# vfd_drive.net
KiCad netlist of a schematic drawn in EAGLE
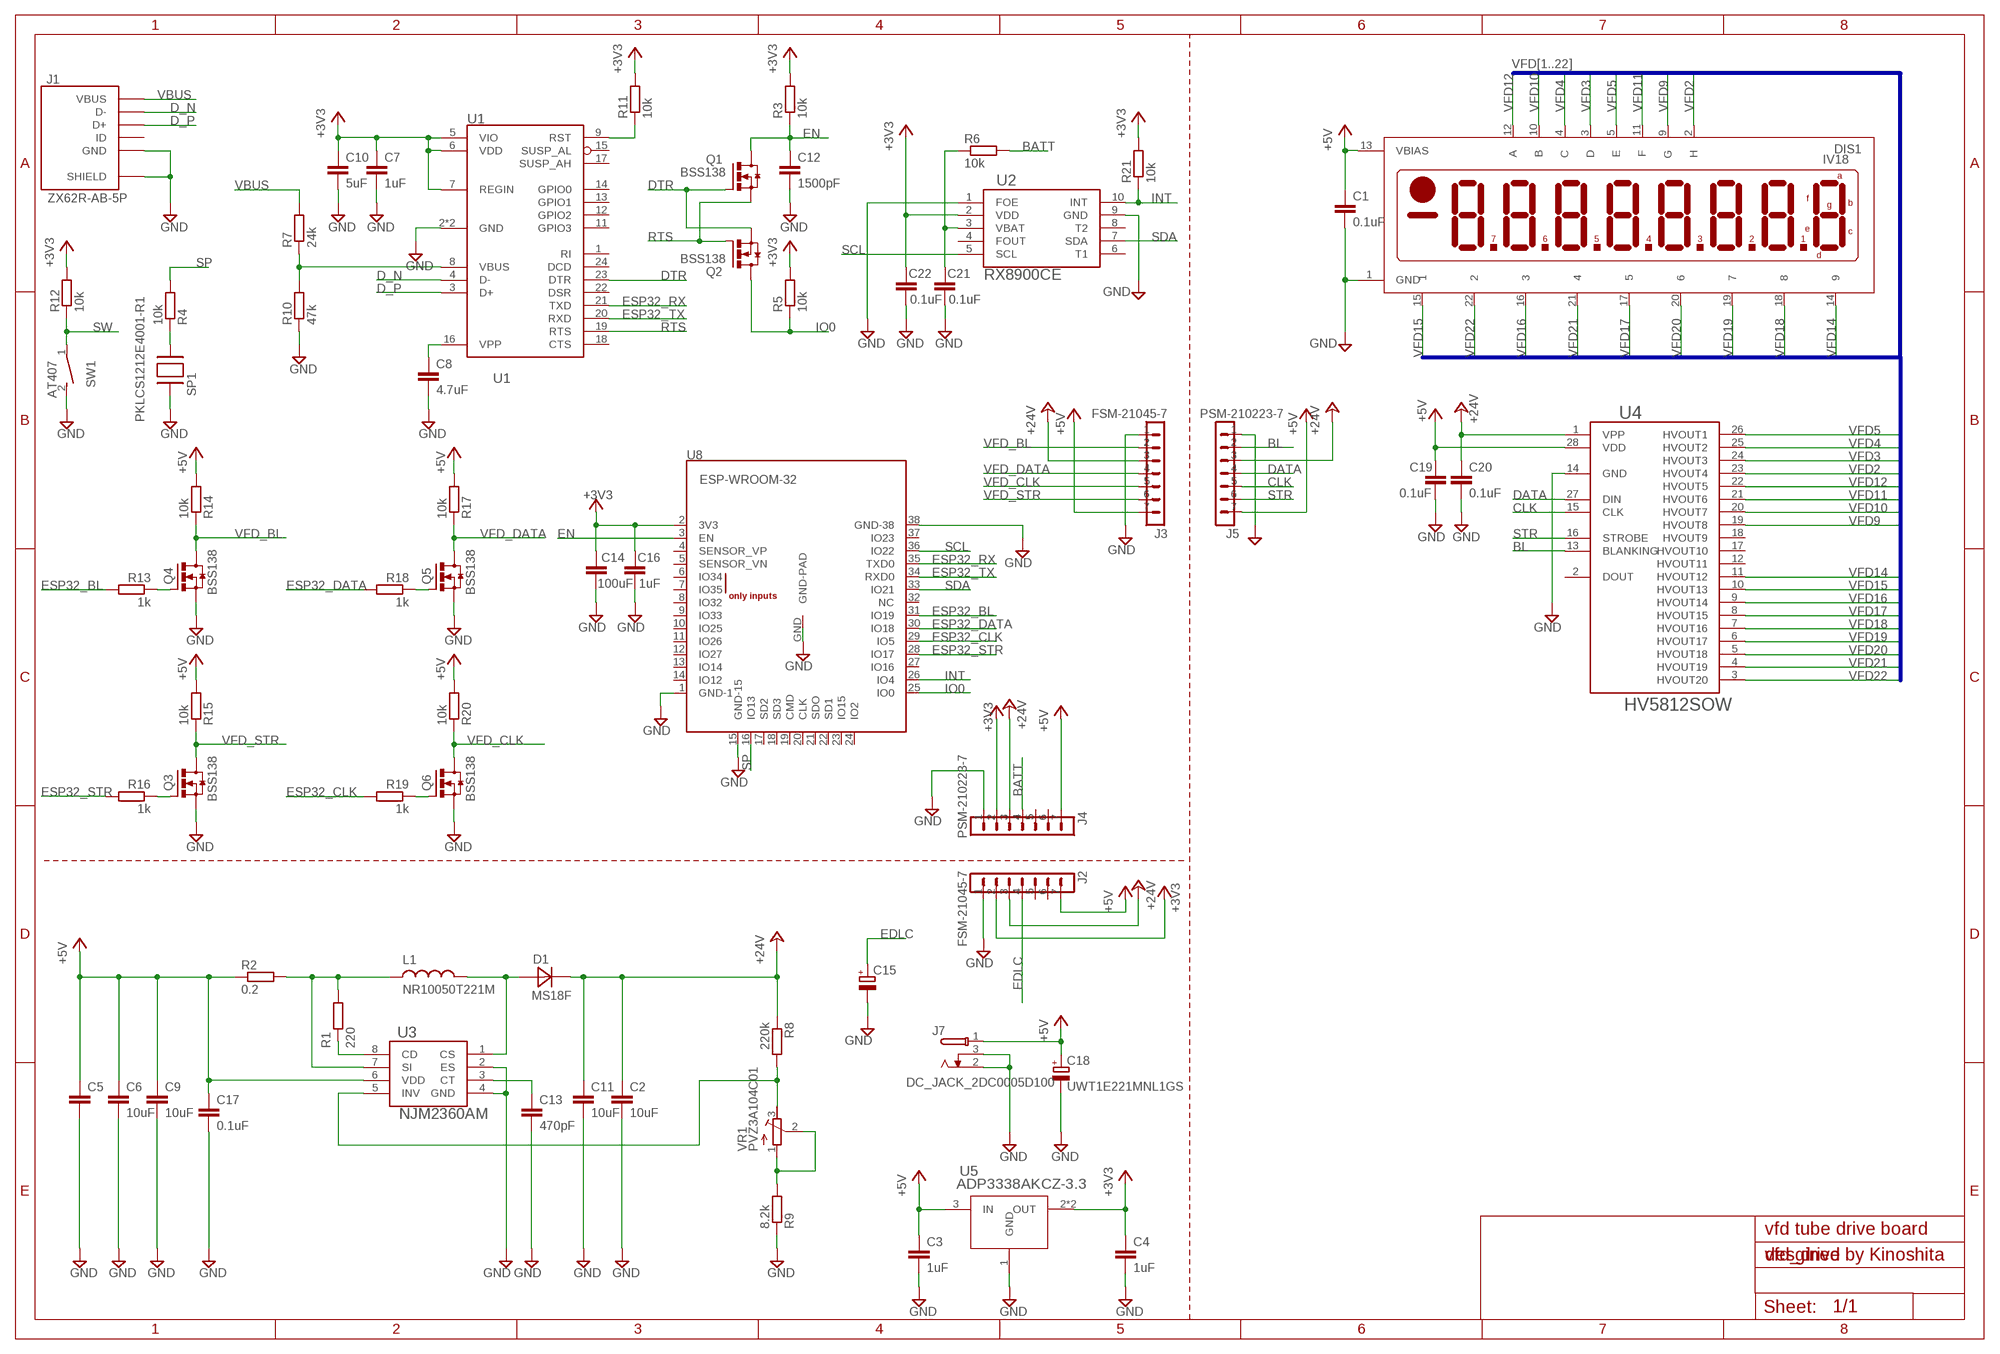
[diagram p0: schematic, sheet 1]

(export (version "E")
  (design (tool "Eeschema 10.0.6"))
  (components
    (comp (ref "C1")
      (value "0.1uF")
      (footprint "eagle-import:C0603")
      (libsource (lib "eagle-import") (part "C-EUC0603"))
    )
    (comp (ref "C2")
      (value "10uF")
      (footprint "eagle-import:C3216")
      (libsource (lib "eagle-import") (part "C-EUC3216"))
    )
    (comp (ref "C3")
      (value "1uF")
      (footprint "eagle-import:C0603")
      (libsource (lib "eagle-import") (part "C-EUC0603"))
    )
    (comp (ref "C4")
      (value "1uF")
      (footprint "eagle-import:C0603")
      (libsource (lib "eagle-import") (part "C-EUC0603"))
    )
    (comp (ref "C5")
      (value "C-EUC3225")
      (footprint "eagle-import:C3225")
      (libsource (lib "eagle-import") (part "C-EUC3225"))
    )
    (comp (ref "C6")
      (value "10uF")
      (footprint "eagle-import:C0603")
      (libsource (lib "eagle-import") (part "C-EUC0603"))
    )
    (comp (ref "C7")
      (value "1uF")
      (footprint "eagle-import:C0603")
      (libsource (lib "eagle-import") (part "C-EUC0603"))
    )
    (comp (ref "C8")
      (value "4.7uF")
      (footprint "eagle-import:C0603")
      (libsource (lib "eagle-import") (part "C-EUC0603"))
    )
    (comp (ref "C9")
      (value "10uF")
      (footprint "eagle-import:C0603")
      (libsource (lib "eagle-import") (part "C-EUC0603"))
    )
    (comp (ref "C10")
      (value "5uF")
      (footprint "eagle-import:C0603")
      (libsource (lib "eagle-import") (part "C-EUC0603"))
    )
    (comp (ref "C11")
      (value "10uF")
      (footprint "eagle-import:C3216")
      (libsource (lib "eagle-import") (part "C-EUC3216"))
    )
    (comp (ref "C12")
      (value "1500pF")
      (footprint "eagle-import:C0603")
      (libsource (lib "eagle-import") (part "C-EUC0603"))
    )
    (comp (ref "C13")
      (value "470pF")
      (footprint "eagle-import:C0603")
      (libsource (lib "eagle-import") (part "C-EUC0603"))
    )
    (comp (ref "C14")
      (value "100uF")
      (footprint "eagle-import:C1206")
      (libsource (lib "eagle-import") (part "C-EUC1206"))
    )
    (comp (ref "C15")
      (value "CPOL-EUSE-5R5-D155VY")
      (footprint "eagle-import:SE-5R5-D155VY")
      (libsource (lib "eagle-import") (part "CPOL-EUSE-5R5-D155VY"))
    )
    (comp (ref "C16")
      (value "1uF")
      (footprint "eagle-import:C0603")
      (libsource (lib "eagle-import") (part "C-EUC0603"))
    )
    (comp (ref "C17")
      (value "0.1uF")
      (footprint "eagle-import:C0603")
      (libsource (lib "eagle-import") (part "C-EUC0603"))
    )
    (comp (ref "C18")
      (value "UWT1E221MNL1GS")
      (footprint "eagle-import:NICHICON-ALMINUM-CAPACITOR-8MM")
      (libsource (lib "eagle-import") (part "UWT1E221MNL1GS"))
    )
    (comp (ref "C19")
      (value "0.1uF")
      (footprint "eagle-import:C0603")
      (libsource (lib "eagle-import") (part "C-EUC0603"))
    )
    (comp (ref "C20")
      (value "0.1uF")
      (footprint "eagle-import:C0603")
      (libsource (lib "eagle-import") (part "C-EUC0603"))
    )
    (comp (ref "C21")
      (value "0.1uF")
      (footprint "eagle-import:C0603")
      (libsource (lib "eagle-import") (part "C-EUC0603"))
    )
    (comp (ref "C22")
      (value "0.1uF")
      (footprint "eagle-import:C0603")
      (libsource (lib "eagle-import") (part "C-EUC0603"))
    )
    (comp (ref "D1")
      (value "MS18F")
      (footprint "eagle-import:SMAF")
      (libsource (lib "eagle-import") (part "MS18F"))
    )
    (comp (ref "DIS1")
      (value "IV18")
      (footprint "eagle-import:IV18")
      (libsource (lib "eagle-import") (part "IV18"))
    )
    (comp (ref "J1")
      (value "ZX62R-AB-5P")
      (footprint "eagle-import:ZX62R-B-5PA")
      (libsource (lib "eagle-import") (part "ZX62R-AB-5P"))
    )
    (comp (ref "J2")
      (value "FSM-21045-7")
      (footprint "eagle-import:FSM-21045-7")
      (libsource (lib "eagle-import") (part "FSM-21045-7"))
    )
    (comp (ref "J3")
      (value "FSM-21045-7")
      (footprint "eagle-import:FSM-21045-7")
      (libsource (lib "eagle-import") (part "FSM-21045-7"))
    )
    (comp (ref "J4")
      (value "PSM-210223-7")
      (footprint "eagle-import:PSM-210223-7")
      (libsource (lib "eagle-import") (part "PSM-210223-7"))
    )
    (comp (ref "J5")
      (value "PSM-210223-7")
      (footprint "eagle-import:PSM-210223-7")
      (libsource (lib "eagle-import") (part "PSM-210223-7"))
    )
    (comp (ref "J7")
      (value "DC_JACK_2DC0005D100")
      (footprint "eagle-import:DC_JACK_2DC0005D100")
      (libsource (lib "eagle-import") (part "DC_JACK_2DC0005D100"))
    )
    (comp (ref "L1")
      (value "NR10050T221M")
      (footprint "eagle-import:NR10050T100M")
      (libsource (lib "eagle-import") (part "NR10050T221M"))
    )
    (comp (ref "Q1")
      (value "BSS138")
      (footprint "eagle-import:SOT23-N-MOSFET")
      (libsource (lib "eagle-import") (part "BSS138"))
    )
    (comp (ref "Q2")
      (value "BSS138")
      (footprint "eagle-import:SOT23-N-MOSFET")
      (libsource (lib "eagle-import") (part "BSS138"))
    )
    (comp (ref "Q3")
      (value "BSS138")
      (footprint "eagle-import:SOT23-N-MOSFET")
      (libsource (lib "eagle-import") (part "BSS138"))
    )
    (comp (ref "Q4")
      (value "BSS138")
      (footprint "eagle-import:SOT23-N-MOSFET")
      (libsource (lib "eagle-import") (part "BSS138"))
    )
    (comp (ref "Q5")
      (value "BSS138")
      (footprint "eagle-import:SOT23-N-MOSFET")
      (libsource (lib "eagle-import") (part "BSS138"))
    )
    (comp (ref "Q6")
      (value "BSS138")
      (footprint "eagle-import:SOT23-N-MOSFET")
      (libsource (lib "eagle-import") (part "BSS138"))
    )
    (comp (ref "R1")
      (value "220")
      (footprint "eagle-import:R0603")
      (libsource (lib "eagle-import") (part "R-EU_R0603"))
    )
    (comp (ref "R2")
      (value "0.2")
      (footprint "eagle-import:R1206")
      (libsource (lib "eagle-import") (part "R-EU_R1206"))
    )
    (comp (ref "R3")
      (value "10k")
      (footprint "eagle-import:R0603")
      (libsource (lib "eagle-import") (part "R-EU_R0603"))
    )
    (comp (ref "R4")
      (value "10k")
      (footprint "eagle-import:R0603")
      (libsource (lib "eagle-import") (part "R-EU_R0603"))
    )
    (comp (ref "R5")
      (value "10k")
      (footprint "eagle-import:R0603")
      (libsource (lib "eagle-import") (part "R-EU_R0603"))
    )
    (comp (ref "R6")
      (value "10k")
      (footprint "eagle-import:R0603")
      (libsource (lib "eagle-import") (part "R-EU_R0603"))
    )
    (comp (ref "R7")
      (value "24k")
      (footprint "eagle-import:R0603")
      (libsource (lib "eagle-import") (part "R-EU_R0603"))
    )
    (comp (ref "R8")
      (value "220k")
      (footprint "eagle-import:R0603")
      (libsource (lib "eagle-import") (part "R-EU_R0603"))
    )
    (comp (ref "R9")
      (value "8.2k")
      (footprint "eagle-import:R0603")
      (libsource (lib "eagle-import") (part "R-EU_R0603"))
    )
    (comp (ref "R10")
      (value "47k")
      (footprint "eagle-import:R0603")
      (libsource (lib "eagle-import") (part "R-EU_R0603"))
    )
    (comp (ref "R11")
      (value "10k")
      (footprint "eagle-import:R0603")
      (libsource (lib "eagle-import") (part "R-EU_R0603"))
    )
    (comp (ref "R12")
      (value "10k")
      (footprint "eagle-import:R0603")
      (libsource (lib "eagle-import") (part "R-EU_R0603"))
    )
    (comp (ref "R13")
      (value "1k")
      (footprint "eagle-import:R0603")
      (libsource (lib "eagle-import") (part "R-EU_R0603"))
    )
    (comp (ref "R14")
      (value "10k")
      (footprint "eagle-import:R0603")
      (libsource (lib "eagle-import") (part "R-EU_R0603"))
    )
    (comp (ref "R15")
      (value "10k")
      (footprint "eagle-import:R0603")
      (libsource (lib "eagle-import") (part "R-EU_R0603"))
    )
    (comp (ref "R16")
      (value "1k")
      (footprint "eagle-import:R0603")
      (libsource (lib "eagle-import") (part "R-EU_R0603"))
    )
    (comp (ref "R17")
      (value "10k")
      (footprint "eagle-import:R0603")
      (libsource (lib "eagle-import") (part "R-EU_R0603"))
    )
    (comp (ref "R18")
      (value "1k")
      (footprint "eagle-import:R0603")
      (libsource (lib "eagle-import") (part "R-EU_R0603"))
    )
    (comp (ref "R19")
      (value "1k")
      (footprint "eagle-import:R0603")
      (libsource (lib "eagle-import") (part "R-EU_R0603"))
    )
    (comp (ref "R20")
      (value "10k")
      (footprint "eagle-import:R0603")
      (libsource (lib "eagle-import") (part "R-EU_R0603"))
    )
    (comp (ref "R21")
      (value "10k")
      (footprint "eagle-import:R0603")
      (libsource (lib "eagle-import") (part "R-EU_R0603"))
    )
    (comp (ref "SP1")
      (value "PKLCS1212E4001-R1")
      (footprint "eagle-import:PKLCS1212E4001-R1")
      (libsource (lib "eagle-import") (part "PKLCS1212E4001-R1"))
    )
    (comp (ref "SW1")
      (value "AT407")
      (footprint "eagle-import:AT407")
      (libsource (lib "eagle-import") (part "AT407"))
    )
    (comp (ref "U1")
      (value "CP2104")
      (footprint "eagle-import:QFN24-SILABS")
      (libsource (lib "eagle-import") (part "CP2104"))
    )
    (comp (ref "U2")
      (value "RX8900CE")
      (footprint "eagle-import:RX8900CE")
      (libsource (lib "eagle-import") (part "RX8900CE"))
    )
    (comp (ref "U3")
      (value "NJM2360AM")
      (footprint "eagle-import:DMP8")
      (libsource (lib "eagle-import") (part "NJM2360AM"))
    )
    (comp (ref "U4")
      (value "HV5812SOW")
      (footprint "eagle-import:SOW28-MICROCHIP")
      (libsource (lib "eagle-import") (part "HV5812SOW"))
    )
    (comp (ref "U5")
      (value "ADP3338AKCZ-3.3")
      (footprint "eagle-import:SOT233")
      (libsource (lib "eagle-import") (part "ADP3338AKCZ-3.3"))
    )
    (comp (ref "U8")
      (value "ESP-WROOM-32")
      (footprint "eagle-import:ESP-WROOM-32")
      (libsource (lib "eagle-import") (part "ESP-WROOM-32"))
    )
    (comp (ref "VR1")
      (value "PVZ3A104C01")
      (footprint "eagle-import:PVZ3A")
      (libsource (lib "eagle-import") (part "PVZ3A104C01"))
    )
  )
  (nets
    (net (code "6") (name "+3V3") (class "Default")
      (node (ref "C10") (pin "1") (pinfunction "1_1") (pintype "passive"))
      (node (ref "C14") (pin "1") (pinfunction "1_1") (pintype "passive"))
      (node (ref "C16") (pin "1") (pinfunction "1_1") (pintype "passive"))
      (node (ref "C22") (pin "1") (pinfunction "1_1") (pintype "passive"))
      (node (ref "C4") (pin "1") (pinfunction "1_1") (pintype "passive"))
      (node (ref "C7") (pin "1") (pinfunction "1_1") (pintype "passive"))
      (node (ref "J2") (pin "2") (pinfunction "2_2") (pintype "bidirectional"))
      (node (ref "J4") (pin "2") (pinfunction "2_2") (pintype "bidirectional"))
      (node (ref "R11") (pin "2") (pinfunction "2_2") (pintype "passive"))
      (node (ref "R12") (pin "2") (pinfunction "2_2") (pintype "passive"))
      (node (ref "R21") (pin "2") (pinfunction "2_2") (pintype "passive"))
      (node (ref "R3") (pin "2") (pinfunction "2_2") (pintype "passive"))
      (node (ref "R5") (pin "2") (pinfunction "2_2") (pintype "passive"))
      (node (ref "U1") (pin "5") (pinfunction "VIO_5") (pintype "bidirectional"))
      (node (ref "U1") (pin "6") (pinfunction "VDD_6") (pintype "bidirectional"))
      (node (ref "U1") (pin "7") (pinfunction "REGIN_7") (pintype "bidirectional"))
      (node (ref "U2") (pin "2") (pinfunction "VDD_2") (pintype "bidirectional"))
      (node (ref "U5") (pin "2") (pinfunction "OUT_2") (pintype "passive"))
      (node (ref "U5") (pin "4") (pinfunction "OUT_4") (pintype "passive"))
      (node (ref "U8") (pin "2") (pinfunction "3V3_2") (pintype "bidirectional"))
    )
    (net (code "7") (name "+5V") (class "Default")
      (node (ref "C1") (pin "1") (pinfunction "1_1") (pintype "passive"))
      (node (ref "C17") (pin "1") (pinfunction "1_1") (pintype "passive"))
      (node (ref "C18") (pin "POS") (pinfunction "+_POS") (pintype "passive"))
      (node (ref "C19") (pin "1") (pinfunction "1_1") (pintype "passive"))
      (node (ref "C3") (pin "1") (pinfunction "1_1") (pintype "passive"))
      (node (ref "C5") (pin "1") (pinfunction "1_1") (pintype "passive"))
      (node (ref "C6") (pin "1") (pinfunction "1_1") (pintype "passive"))
      (node (ref "C9") (pin "1") (pinfunction "1_1") (pintype "passive"))
      (node (ref "DIS1") (pin "13") (pinfunction "VBIAS_13") (pintype "power_in"))
      (node (ref "J2") (pin "7") (pinfunction "7_7") (pintype "bidirectional"))
      (node (ref "J3") (pin "7") (pinfunction "7_7") (pintype "bidirectional"))
      (node (ref "J4") (pin "7") (pinfunction "7_7") (pintype "bidirectional"))
      (node (ref "J5") (pin "7") (pinfunction "7_7") (pintype "bidirectional"))
      (node (ref "J7") (pin "1") (pinfunction "1_1") (pintype "passive"))
      (node (ref "R14") (pin "2") (pinfunction "2_2") (pintype "passive"))
      (node (ref "R15") (pin "2") (pinfunction "2_2") (pintype "passive"))
      (node (ref "R17") (pin "2") (pinfunction "2_2") (pintype "passive"))
      (node (ref "R2") (pin "1") (pinfunction "1_1") (pintype "passive"))
      (node (ref "R20") (pin "2") (pinfunction "2_2") (pintype "passive"))
      (node (ref "U3") (pin "6") (pinfunction "VDD_6") (pintype "bidirectional"))
      (node (ref "U4") (pin "28") (pinfunction "VDD_28") (pintype "bidirectional"))
      (node (ref "U5") (pin "3") (pinfunction "IN_3") (pintype "passive"))
    )
    (net (code "8") (name "+24V") (class "Default")
      (node (ref "C11") (pin "1") (pinfunction "1_1") (pintype "passive"))
      (node (ref "C2") (pin "1") (pinfunction "1_1") (pintype "passive"))
      (node (ref "C20") (pin "1") (pinfunction "1_1") (pintype "passive"))
      (node (ref "D1") (pin "K") (pinfunction "C_K") (pintype "passive"))
      (node (ref "J2") (pin "3") (pinfunction "3_3") (pintype "bidirectional"))
      (node (ref "J3") (pin "3") (pinfunction "3_3") (pintype "bidirectional"))
      (node (ref "J4") (pin "3") (pinfunction "3_3") (pintype "bidirectional"))
      (node (ref "J5") (pin "3") (pinfunction "3_3") (pintype "bidirectional"))
      (node (ref "R8") (pin "1") (pinfunction "1_1") (pintype "passive"))
      (node (ref "U4") (pin "1") (pinfunction "VPP_1") (pintype "bidirectional"))
    )
    (net (code "9") (name "/BATT") (class "Default")
      (node (ref "J4") (pin "4") (pinfunction "4_4") (pintype "bidirectional"))
      (node (ref "R6") (pin "2") (pinfunction "2_2") (pintype "passive"))
    )
    (net (code "10") (name "/BL") (class "Default")
      (node (ref "J5") (pin "2") (pinfunction "2_2") (pintype "bidirectional"))
      (node (ref "U4") (pin "13") (pinfunction "BLANKING_13") (pintype "bidirectional"))
    )
    (net (code "11") (name "/CLK") (class "Default")
      (node (ref "J5") (pin "5") (pinfunction "5_5") (pintype "bidirectional"))
      (node (ref "U4") (pin "15") (pinfunction "CLK_15") (pintype "bidirectional"))
    )
    (net (code "12") (name "/DATA") (class "Default")
      (node (ref "J5") (pin "4") (pinfunction "4_4") (pintype "bidirectional"))
      (node (ref "U4") (pin "27") (pinfunction "DIN_27") (pintype "bidirectional"))
    )
    (net (code "13") (name "/DTR") (class "Default")
      (node (ref "Q1") (pin "G") (pinfunction "G_G") (pintype "passive"))
      (node (ref "Q2") (pin "S") (pinfunction "S_S") (pintype "passive"))
      (node (ref "U1") (pin "23") (pinfunction "DTR_23") (pintype "bidirectional"))
    )
    (net (code "14") (name "/D_N") (class "Default")
      (node (ref "J1") (pin "D-") (pinfunction "D-_D-") (pintype "bidirectional"))
      (node (ref "U1") (pin "4") (pinfunction "D-_4") (pintype "bidirectional"))
    )
    (net (code "15") (name "/D_P") (class "Default")
      (node (ref "J1") (pin "D+") (pinfunction "D+_D+") (pintype "bidirectional"))
      (node (ref "U1") (pin "3") (pinfunction "D+_3") (pintype "bidirectional"))
    )
    (net (code "16") (name "/EDLC") (class "Default")
      (node (ref "C15") (pin "POS") (pinfunction "+_POS") (pintype "passive"))
      (node (ref "J2") (pin "4") (pinfunction "4_4") (pintype "bidirectional"))
    )
    (net (code "17") (name "/EN") (class "Default")
      (node (ref "C12") (pin "1") (pinfunction "1_1") (pintype "passive"))
      (node (ref "Q1") (pin "D") (pinfunction "D_D") (pintype "passive"))
      (node (ref "R3") (pin "1") (pinfunction "1_1") (pintype "passive"))
      (node (ref "U8") (pin "3") (pinfunction "EN_3") (pintype "bidirectional"))
    )
    (net (code "18") (name "/ESP32_BL") (class "Default")
      (node (ref "R13") (pin "2") (pinfunction "2_2") (pintype "passive"))
      (node (ref "U8") (pin "31") (pinfunction "IO19_31") (pintype "bidirectional"))
    )
    (net (code "19") (name "/ESP32_CLK") (class "Default")
      (node (ref "R19") (pin "2") (pinfunction "2_2") (pintype "passive"))
      (node (ref "U8") (pin "29") (pinfunction "IO5_29") (pintype "bidirectional"))
    )
    (net (code "20") (name "/ESP32_DATA") (class "Default")
      (node (ref "R18") (pin "2") (pinfunction "2_2") (pintype "passive"))
      (node (ref "U8") (pin "30") (pinfunction "IO18_30") (pintype "bidirectional"))
    )
    (net (code "21") (name "/ESP32_RX") (class "Default")
      (node (ref "U1") (pin "21") (pinfunction "TXD_21") (pintype "bidirectional"))
      (node (ref "U8") (pin "35") (pinfunction "TXD0_35") (pintype "bidirectional"))
    )
    (net (code "22") (name "/ESP32_STR") (class "Default")
      (node (ref "R16") (pin "2") (pinfunction "2_2") (pintype "passive"))
      (node (ref "U8") (pin "28") (pinfunction "IO17_28") (pintype "bidirectional"))
    )
    (net (code "23") (name "/ESP32_TX") (class "Default")
      (node (ref "U1") (pin "20") (pinfunction "RXD_20") (pintype "bidirectional"))
      (node (ref "U8") (pin "34") (pinfunction "RXD0_34") (pintype "bidirectional"))
    )
    (net (code "24") (name "/INT") (class "Default")
      (node (ref "R21") (pin "1") (pinfunction "1_1") (pintype "passive"))
      (node (ref "U2") (pin "10") (pinfunction "INT_10") (pintype "bidirectional"))
      (node (ref "U8") (pin "26") (pinfunction "IO4_26") (pintype "bidirectional"))
    )
    (net (code "25") (name "/IO0") (class "Default")
      (node (ref "Q2") (pin "D") (pinfunction "D_D") (pintype "passive"))
      (node (ref "R5") (pin "1") (pinfunction "1_1") (pintype "passive"))
      (node (ref "U8") (pin "25") (pinfunction "IO0_25") (pintype "bidirectional"))
    )
    (net (code "26") (name "/RTS") (class "Default")
      (node (ref "Q1") (pin "S") (pinfunction "S_S") (pintype "passive"))
      (node (ref "Q2") (pin "G") (pinfunction "G_G") (pintype "passive"))
      (node (ref "U1") (pin "19") (pinfunction "RTS_19") (pintype "bidirectional"))
    )
    (net (code "27") (name "/SCL") (class "Default")
      (node (ref "U2") (pin "5") (pinfunction "SCL_5") (pintype "bidirectional"))
      (node (ref "U8") (pin "36") (pinfunction "IO22_36") (pintype "bidirectional"))
    )
    (net (code "28") (name "/SDA") (class "Default")
      (node (ref "U2") (pin "7") (pinfunction "SDA_7") (pintype "bidirectional"))
      (node (ref "U8") (pin "33") (pinfunction "IO21_33") (pintype "bidirectional"))
    )
    (net (code "29") (name "/SP") (class "Default")
      (node (ref "R4") (pin "2") (pinfunction "2_2") (pintype "passive"))
      (node (ref "U8") (pin "16") (pinfunction "IO13_16") (pintype "bidirectional"))
    )
    (net (code "30") (name "/STR") (class "Default")
      (node (ref "J5") (pin "6") (pinfunction "6_6") (pintype "bidirectional"))
      (node (ref "U4") (pin "16") (pinfunction "STROBE_16") (pintype "bidirectional"))
    )
    (net (code "31") (name "/SW") (class "Default")
      (node (ref "R12") (pin "1") (pinfunction "1_1") (pintype "passive"))
      (node (ref "SW1") (pin "1") (pinfunction "1_1") (pintype "passive"))
    )
    (net (code "32") (name "/VBUS") (class "Default")
      (node (ref "J1") (pin "VCC") (pinfunction "VBUS_VCC") (pintype "bidirectional"))
      (node (ref "R7") (pin "2") (pinfunction "2_2") (pintype "passive"))
    )
    (net (code "33") (name "/VFD2") (class "Default")
      (node (ref "DIS1") (pin "2") (pinfunction "H_2") (pintype "passive"))
      (node (ref "U4") (pin "23") (pinfunction "HVOUT4_23") (pintype "bidirectional"))
    )
    (net (code "34") (name "/VFD3") (class "Default")
      (node (ref "DIS1") (pin "3") (pinfunction "D_3") (pintype "passive"))
      (node (ref "U4") (pin "24") (pinfunction "HVOUT3_24") (pintype "bidirectional"))
    )
    (net (code "35") (name "/VFD4") (class "Default")
      (node (ref "DIS1") (pin "4") (pinfunction "C_4") (pintype "passive"))
      (node (ref "U4") (pin "25") (pinfunction "HVOUT2_25") (pintype "bidirectional"))
    )
    (net (code "36") (name "/VFD5") (class "Default")
      (node (ref "DIS1") (pin "5") (pinfunction "E_5") (pintype "passive"))
      (node (ref "U4") (pin "26") (pinfunction "HVOUT1_26") (pintype "bidirectional"))
    )
    (net (code "37") (name "/VFD9") (class "Default")
      (node (ref "DIS1") (pin "9") (pinfunction "G_9") (pintype "passive"))
      (node (ref "U4") (pin "19") (pinfunction "HVOUT8_19") (pintype "bidirectional"))
    )
    (net (code "38") (name "/VFD10") (class "Default")
      (node (ref "DIS1") (pin "10") (pinfunction "B_10") (pintype "passive"))
      (node (ref "U4") (pin "20") (pinfunction "HVOUT7_20") (pintype "bidirectional"))
    )
    (net (code "39") (name "/VFD11") (class "Default")
      (node (ref "DIS1") (pin "11") (pinfunction "F_11") (pintype "passive"))
      (node (ref "U4") (pin "21") (pinfunction "HVOUT6_21") (pintype "bidirectional"))
    )
    (net (code "40") (name "/VFD12") (class "Default")
      (node (ref "DIS1") (pin "12") (pinfunction "A_12") (pintype "passive"))
      (node (ref "U4") (pin "22") (pinfunction "HVOUT5_22") (pintype "bidirectional"))
    )
    (net (code "41") (name "/VFD14") (class "Default")
      (node (ref "DIS1") (pin "14") (pinfunction "9_14") (pintype "passive"))
      (node (ref "U4") (pin "11") (pinfunction "HVOUT12_11") (pintype "bidirectional"))
    )
    (net (code "42") (name "/VFD15") (class "Default")
      (node (ref "DIS1") (pin "15") (pinfunction "1_15") (pintype "passive"))
      (node (ref "U4") (pin "10") (pinfunction "HVOUT13_10") (pintype "bidirectional"))
    )
    (net (code "43") (name "/VFD16") (class "Default")
      (node (ref "DIS1") (pin "16") (pinfunction "3_16") (pintype "passive"))
      (node (ref "U4") (pin "9") (pinfunction "HVOUT14_9") (pintype "bidirectional"))
    )
    (net (code "44") (name "/VFD17") (class "Default")
      (node (ref "DIS1") (pin "17") (pinfunction "5_17") (pintype "passive"))
      (node (ref "U4") (pin "8") (pinfunction "HVOUT15_8") (pintype "bidirectional"))
    )
    (net (code "45") (name "/VFD18") (class "Default")
      (node (ref "DIS1") (pin "18") (pinfunction "8_18") (pintype "passive"))
      (node (ref "U4") (pin "7") (pinfunction "HVOUT16_7") (pintype "bidirectional"))
    )
    (net (code "46") (name "/VFD19") (class "Default")
      (node (ref "DIS1") (pin "19") (pinfunction "7_19") (pintype "passive"))
      (node (ref "U4") (pin "6") (pinfunction "HVOUT17_6") (pintype "bidirectional"))
    )
    (net (code "47") (name "/VFD20") (class "Default")
      (node (ref "DIS1") (pin "20") (pinfunction "6_20") (pintype "passive"))
      (node (ref "U4") (pin "5") (pinfunction "HVOUT18_5") (pintype "bidirectional"))
    )
    (net (code "48") (name "/VFD21") (class "Default")
      (node (ref "DIS1") (pin "21") (pinfunction "4_21") (pintype "passive"))
      (node (ref "U4") (pin "4") (pinfunction "HVOUT19_4") (pintype "bidirectional"))
    )
    (net (code "49") (name "/VFD22") (class "Default")
      (node (ref "DIS1") (pin "22") (pinfunction "2_22") (pintype "passive"))
      (node (ref "U4") (pin "3") (pinfunction "HVOUT20_3") (pintype "bidirectional"))
    )
    (net (code "51") (name "/VFD_BL") (class "Default")
      (node (ref "J3") (pin "2") (pinfunction "2_2") (pintype "bidirectional"))
      (node (ref "Q4") (pin "D") (pinfunction "D_D") (pintype "passive"))
      (node (ref "R14") (pin "1") (pinfunction "1_1") (pintype "passive"))
    )
    (net (code "52") (name "/VFD_CLK") (class "Default")
      (node (ref "J3") (pin "5") (pinfunction "5_5") (pintype "bidirectional"))
      (node (ref "Q6") (pin "D") (pinfunction "D_D") (pintype "passive"))
      (node (ref "R20") (pin "1") (pinfunction "1_1") (pintype "passive"))
    )
    (net (code "53") (name "/VFD_DATA") (class "Default")
      (node (ref "J3") (pin "4") (pinfunction "4_4") (pintype "bidirectional"))
      (node (ref "Q5") (pin "D") (pinfunction "D_D") (pintype "passive"))
      (node (ref "R17") (pin "1") (pinfunction "1_1") (pintype "passive"))
    )
    (net (code "54") (name "/VFD_STR") (class "Default")
      (node (ref "J3") (pin "6") (pinfunction "6_6") (pintype "bidirectional"))
      (node (ref "Q3") (pin "D") (pinfunction "D_D") (pintype "passive"))
      (node (ref "R15") (pin "1") (pinfunction "1_1") (pintype "passive"))
    )
    (net (code "55") (name "GND") (class "Default")
      (node (ref "C1") (pin "2") (pinfunction "2_2") (pintype "passive"))
      (node (ref "C10") (pin "2") (pinfunction "2_2") (pintype "passive"))
      (node (ref "C11") (pin "2") (pinfunction "2_2") (pintype "passive"))
      (node (ref "C12") (pin "2") (pinfunction "2_2") (pintype "passive"))
      (node (ref "C13") (pin "2") (pinfunction "2_2") (pintype "passive"))
      (node (ref "C14") (pin "2") (pinfunction "2_2") (pintype "passive"))
      (node (ref "C15") (pin "NEG") (pinfunction "-_NEG") (pintype "passive"))
      (node (ref "C16") (pin "2") (pinfunction "2_2") (pintype "passive"))
      (node (ref "C17") (pin "2") (pinfunction "2_2") (pintype "passive"))
      (node (ref "C18") (pin "NEG") (pinfunction "-_NEG") (pintype "passive"))
      (node (ref "C19") (pin "2") (pinfunction "2_2") (pintype "passive"))
      (node (ref "C2") (pin "2") (pinfunction "2_2") (pintype "passive"))
      (node (ref "C20") (pin "2") (pinfunction "2_2") (pintype "passive"))
      (node (ref "C21") (pin "2") (pinfunction "2_2") (pintype "passive"))
      (node (ref "C22") (pin "2") (pinfunction "2_2") (pintype "passive"))
      (node (ref "C3") (pin "2") (pinfunction "2_2") (pintype "passive"))
      (node (ref "C4") (pin "2") (pinfunction "2_2") (pintype "passive"))
      (node (ref "C5") (pin "2") (pinfunction "2_2") (pintype "passive"))
      (node (ref "C6") (pin "2") (pinfunction "2_2") (pintype "passive"))
      (node (ref "C7") (pin "2") (pinfunction "2_2") (pintype "passive"))
      (node (ref "C8") (pin "2") (pinfunction "2_2") (pintype "passive"))
      (node (ref "C9") (pin "2") (pinfunction "2_2") (pintype "passive"))
      (node (ref "DIS1") (pin "1") (pinfunction "GND_1") (pintype "power_in"))
      (node (ref "J1") (pin "GND") (pinfunction "GND_GND") (pintype "bidirectional"))
      (node (ref "J1") (pin "SHIELD@1") (pinfunction "SHIELD_SHIELD@1") (pintype "bidirectional"))
      (node (ref "J1") (pin "SHIELD@2") (pinfunction "SHIELD_SHIELD@2") (pintype "bidirectional"))
      (node (ref "J1") (pin "SHIELD@3") (pinfunction "SHIELD_SHIELD@3") (pintype "bidirectional"))
      (node (ref "J1") (pin "SHIELD@4") (pinfunction "SHIELD_SHIELD@4") (pintype "bidirectional"))
      (node (ref "J2") (pin "1") (pinfunction "1_1") (pintype "bidirectional"))
      (node (ref "J3") (pin "1") (pinfunction "1_1") (pintype "bidirectional"))
      (node (ref "J4") (pin "1") (pinfunction "1_1") (pintype "bidirectional"))
      (node (ref "J5") (pin "1") (pinfunction "1_1") (pintype "bidirectional"))
      (node (ref "J7") (pin "2") (pinfunction "2_2") (pintype "passive"))
      (node (ref "J7") (pin "3") (pinfunction "3_3") (pintype "passive"))
      (node (ref "Q3") (pin "S") (pinfunction "S_S") (pintype "passive"))
      (node (ref "Q4") (pin "S") (pinfunction "S_S") (pintype "passive"))
      (node (ref "Q5") (pin "S") (pinfunction "S_S") (pintype "passive"))
      (node (ref "Q6") (pin "S") (pinfunction "S_S") (pintype "passive"))
      (node (ref "R10") (pin "1") (pinfunction "1_1") (pintype "passive"))
      (node (ref "R9") (pin "1") (pinfunction "1_1") (pintype "passive"))
      (node (ref "SP1") (pin "2") (pinfunction "P$2_2") (pintype "bidirectional"))
      (node (ref "SW1") (pin "2") (pinfunction "2_2") (pintype "passive"))
      (node (ref "U1") (pin "2") (pinfunction "GND_2") (pintype "bidirectional"))
      (node (ref "U1") (pin "25") (pinfunction "GND_25") (pintype "bidirectional"))
      (node (ref "U2") (pin "1") (pinfunction "FOE_1") (pintype "bidirectional"))
      (node (ref "U2") (pin "9") (pinfunction "GND_9") (pintype "bidirectional"))
      (node (ref "U3") (pin "2") (pinfunction "ES_2") (pintype "bidirectional"))
      (node (ref "U3") (pin "4") (pinfunction "GND_4") (pintype "bidirectional"))
      (node (ref "U4") (pin "14") (pinfunction "GND_14") (pintype "bidirectional"))
      (node (ref "U5") (pin "1") (pinfunction "GND_1") (pintype "passive"))
      (node (ref "U8") (pin "1") (pinfunction "GND-1_1") (pintype "bidirectional"))
      (node (ref "U8") (pin "15") (pinfunction "GND-15_15") (pintype "bidirectional"))
      (node (ref "U8") (pin "38") (pinfunction "GND-38_38") (pintype "bidirectional"))
      (node (ref "U8") (pin "GND") (pinfunction "GND-PAD_GND") (pintype "bidirectional"))
    )
    (net (code "56") (name "Net-(L1-1)") (class "Default")
      (node (ref "L1") (pin "P$1") (pinfunction "1_P$1") (pintype "passive"))
      (node (ref "R1") (pin "2") (pinfunction "2_2") (pintype "passive"))
      (node (ref "R2") (pin "2") (pinfunction "2_2") (pintype "passive"))
      (node (ref "U3") (pin "7") (pinfunction "SI_7") (pintype "bidirectional"))
    )
    (net (code "57") (name "Net-(L1-2)") (class "Default")
      (node (ref "D1") (pin "A") (pinfunction "A_A") (pintype "passive"))
      (node (ref "L1") (pin "P$2") (pinfunction "2_P$2") (pintype "passive"))
      (node (ref "U3") (pin "1") (pinfunction "CS_1") (pintype "bidirectional"))
    )
    (net (code "58") (name "Net-(Q3-PadG)") (class "Default")
      (node (ref "Q3") (pin "G") (pinfunction "G_G") (pintype "passive"))
      (node (ref "R16") (pin "1") (pinfunction "1_1") (pintype "passive"))
    )
    (net (code "59") (name "Net-(Q4-PadG)") (class "Default")
      (node (ref "Q4") (pin "G") (pinfunction "G_G") (pintype "passive"))
      (node (ref "R13") (pin "1") (pinfunction "1_1") (pintype "passive"))
    )
    (net (code "60") (name "Net-(Q5-PadG)") (class "Default")
      (node (ref "Q5") (pin "G") (pinfunction "G_G") (pintype "passive"))
      (node (ref "R18") (pin "1") (pinfunction "1_1") (pintype "passive"))
    )
    (net (code "61") (name "Net-(Q6-PadG)") (class "Default")
      (node (ref "Q6") (pin "G") (pinfunction "G_G") (pintype "passive"))
      (node (ref "R19") (pin "1") (pinfunction "1_1") (pintype "passive"))
    )
    (net (code "62") (name "Net-(R4-Pad1)") (class "Default")
      (node (ref "R4") (pin "1") (pinfunction "1_1") (pintype "passive"))
      (node (ref "SP1") (pin "1") (pinfunction "1_1") (pintype "bidirectional"))
    )
    (net (code "63") (name "Net-(U1-RST)") (class "Default")
      (node (ref "R11") (pin "1") (pinfunction "1_1") (pintype "passive"))
      (node (ref "U1") (pin "9") (pinfunction "RST_9") (pintype "bidirectional"))
    )
    (net (code "64") (name "Net-(U1-VBUS)") (class "Default")
      (node (ref "R10") (pin "2") (pinfunction "2_2") (pintype "passive"))
      (node (ref "R7") (pin "1") (pinfunction "1_1") (pintype "passive"))
      (node (ref "U1") (pin "8") (pinfunction "VBUS_8") (pintype "bidirectional"))
    )
    (net (code "65") (name "Net-(U1-VPP)") (class "Default")
      (node (ref "C8") (pin "1") (pinfunction "1_1") (pintype "passive"))
      (node (ref "U1") (pin "16") (pinfunction "VPP_16") (pintype "bidirectional"))
    )
    (net (code "66") (name "Net-(U2-VBAT)") (class "Default")
      (node (ref "C21") (pin "1") (pinfunction "1_1") (pintype "passive"))
      (node (ref "R6") (pin "1") (pinfunction "1_1") (pintype "passive"))
      (node (ref "U2") (pin "3") (pinfunction "VBAT_3") (pintype "bidirectional"))
    )
    (net (code "67") (name "Net-(U3-CD)") (class "Default")
      (node (ref "R1") (pin "1") (pinfunction "1_1") (pintype "passive"))
      (node (ref "U3") (pin "8") (pinfunction "CD_8") (pintype "bidirectional"))
    )
    (net (code "68") (name "Net-(U3-CT)") (class "Default")
      (node (ref "C13") (pin "1") (pinfunction "1_1") (pintype "passive"))
      (node (ref "U3") (pin "3") (pinfunction "CT_3") (pintype "bidirectional"))
    )
    (net (code "69") (name "Net-(U3-INV)") (class "Default")
      (node (ref "R8") (pin "2") (pinfunction "2_2") (pintype "passive"))
      (node (ref "U3") (pin "5") (pinfunction "INV_5") (pintype "bidirectional"))
      (node (ref "VR1") (pin "3") (pinfunction "A_3") (pintype "passive"))
    )
    (net (code "70") (name "Net-(VR1-E)") (class "Default")
      (node (ref "R9") (pin "2") (pinfunction "2_2") (pintype "passive"))
      (node (ref "VR1") (pin "1") (pinfunction "E_1") (pintype "passive"))
      (node (ref "VR1") (pin "2") (pinfunction "S_2") (pintype "passive"))
    )
    (net (code "71") (name "unconnected-(J1-PadID)") (class "Default")
      (node (ref "J1") (pin "ID") (pinfunction "ID_ID") (pintype "bidirectional"))
    )
    (net (code "72") (name "unconnected-(J2-Pad5)") (class "Default")
      (node (ref "J2") (pin "5") (pinfunction "5_5") (pintype "bidirectional"))
    )
    (net (code "73") (name "unconnected-(J2-Pad6)") (class "Default")
      (node (ref "J2") (pin "6") (pinfunction "6_6") (pintype "bidirectional"))
    )
    (net (code "74") (name "unconnected-(J4-Pad5)") (class "Default")
      (node (ref "J4") (pin "5") (pinfunction "5_5") (pintype "bidirectional"))
    )
    (net (code "75") (name "unconnected-(J4-Pad6)") (class "Default")
      (node (ref "J4") (pin "6") (pinfunction "6_6") (pintype "bidirectional"))
    )
    (net (code "76") (name "unconnected-(U1-CTS-Pad18)") (class "Default")
      (node (ref "U1") (pin "18") (pinfunction "CTS_18") (pintype "bidirectional"))
    )
    (net (code "77") (name "unconnected-(U1-DCD-Pad24)") (class "Default")
      (node (ref "U1") (pin "24") (pinfunction "DCD_24") (pintype "bidirectional"))
    )
    (net (code "78") (name "unconnected-(U1-DSR-Pad22)") (class "Default")
      (node (ref "U1") (pin "22") (pinfunction "DSR_22") (pintype "bidirectional"))
    )
    (net (code "79") (name "unconnected-(U1-GPIO0-Pad14)") (class "Default")
      (node (ref "U1") (pin "14") (pinfunction "GPIO0_14") (pintype "bidirectional"))
    )
    (net (code "80") (name "unconnected-(U1-GPIO1-Pad13)") (class "Default")
      (node (ref "U1") (pin "13") (pinfunction "GPIO1_13") (pintype "bidirectional"))
    )
    (net (code "81") (name "unconnected-(U1-GPIO2-Pad12)") (class "Default")
      (node (ref "U1") (pin "12") (pinfunction "GPIO2_12") (pintype "bidirectional"))
    )
    (net (code "82") (name "unconnected-(U1-GPIO3-Pad11)") (class "Default")
      (node (ref "U1") (pin "11") (pinfunction "GPIO3_11") (pintype "bidirectional"))
    )
    (net (code "83") (name "unconnected-(U1-RI-Pad1)") (class "Default")
      (node (ref "U1") (pin "1") (pinfunction "RI_1") (pintype "bidirectional"))
    )
    (net (code "84") (name "unconnected-(U1-SUSP_AH-Pad17)") (class "Default")
      (node (ref "U1") (pin "17") (pinfunction "SUSP_AH_17") (pintype "output"))
    )
    (net (code "85") (name "unconnected-(U1-SUSP_AL-Pad15)") (class "Default")
      (node (ref "U1") (pin "15") (pinfunction "SUSP_AL_15") (pintype "bidirectional"))
    )
    (net (code "86") (name "unconnected-(U2-FOUT-Pad4)") (class "Default")
      (node (ref "U2") (pin "4") (pinfunction "FOUT_4") (pintype "bidirectional"))
    )
    (net (code "87") (name "unconnected-(U2-T1-Pad6)") (class "Default")
      (node (ref "U2") (pin "6") (pinfunction "T1_6") (pintype "bidirectional"))
    )
    (net (code "88") (name "unconnected-(U2-T2-Pad8)") (class "Default")
      (node (ref "U2") (pin "8") (pinfunction "T2_8") (pintype "bidirectional"))
    )
    (net (code "89") (name "unconnected-(U4-DOUT-Pad2)") (class "Default")
      (node (ref "U4") (pin "2") (pinfunction "DOUT_2") (pintype "bidirectional"))
    )
    (net (code "90") (name "unconnected-(U4-HVOUT9-Pad18)") (class "Default")
      (node (ref "U4") (pin "18") (pinfunction "HVOUT9_18") (pintype "bidirectional"))
    )
    (net (code "91") (name "unconnected-(U4-HVOUT10-Pad17)") (class "Default")
      (node (ref "U4") (pin "17") (pinfunction "HVOUT10_17") (pintype "bidirectional"))
    )
    (net (code "92") (name "unconnected-(U4-HVOUT11-Pad12)") (class "Default")
      (node (ref "U4") (pin "12") (pinfunction "HVOUT11_12") (pintype "bidirectional"))
    )
    (net (code "93") (name "unconnected-(U8-CLK-Pad20)") (class "Default")
      (node (ref "U8") (pin "20") (pinfunction "CLK_20") (pintype "bidirectional"))
    )
    (net (code "94") (name "unconnected-(U8-CMD-Pad19)") (class "Default")
      (node (ref "U8") (pin "19") (pinfunction "CMD_19") (pintype "bidirectional"))
    )
    (net (code "95") (name "unconnected-(U8-IO2-Pad24)") (class "Default")
      (node (ref "U8") (pin "24") (pinfunction "IO2_24") (pintype "bidirectional"))
    )
    (net (code "96") (name "unconnected-(U8-IO12-Pad14)") (class "Default")
      (node (ref "U8") (pin "14") (pinfunction "IO12_14") (pintype "bidirectional"))
    )
    (net (code "97") (name "unconnected-(U8-IO14-Pad13)") (class "Default")
      (node (ref "U8") (pin "13") (pinfunction "IO14_13") (pintype "bidirectional"))
    )
    (net (code "98") (name "unconnected-(U8-IO15-Pad23)") (class "Default")
      (node (ref "U8") (pin "23") (pinfunction "IO15_23") (pintype "bidirectional"))
    )
    (net (code "99") (name "unconnected-(U8-IO16-Pad27)") (class "Default")
      (node (ref "U8") (pin "27") (pinfunction "IO16_27") (pintype "bidirectional"))
    )
    (net (code "100") (name "unconnected-(U8-IO23-Pad37)") (class "Default")
      (node (ref "U8") (pin "37") (pinfunction "IO23_37") (pintype "bidirectional"))
    )
    (net (code "101") (name "unconnected-(U8-IO25-Pad10)") (class "Default")
      (node (ref "U8") (pin "10") (pinfunction "IO25_10") (pintype "bidirectional"))
    )
    (net (code "102") (name "unconnected-(U8-IO26-Pad11)") (class "Default")
      (node (ref "U8") (pin "11") (pinfunction "IO26_11") (pintype "bidirectional"))
    )
    (net (code "103") (name "unconnected-(U8-IO27-Pad12)") (class "Default")
      (node (ref "U8") (pin "12") (pinfunction "IO27_12") (pintype "bidirectional"))
    )
    (net (code "104") (name "unconnected-(U8-IO32-Pad8)") (class "Default")
      (node (ref "U8") (pin "8") (pinfunction "IO32_8") (pintype "bidirectional"))
    )
    (net (code "105") (name "unconnected-(U8-IO33-Pad9)") (class "Default")
      (node (ref "U8") (pin "9") (pinfunction "IO33_9") (pintype "bidirectional"))
    )
    (net (code "106") (name "unconnected-(U8-IO34-Pad6)") (class "Default")
      (node (ref "U8") (pin "6") (pinfunction "IO34_6") (pintype "input"))
    )
    (net (code "107") (name "unconnected-(U8-IO35-Pad7)") (class "Default")
      (node (ref "U8") (pin "7") (pinfunction "IO35_7") (pintype "input"))
    )
    (net (code "108") (name "unconnected-(U8-NC-Pad32)") (class "Default")
      (node (ref "U8") (pin "32") (pinfunction "NC_32") (pintype "bidirectional"))
    )
    (net (code "109") (name "unconnected-(U8-SD1-Pad22)") (class "Default")
      (node (ref "U8") (pin "22") (pinfunction "SD1_22") (pintype "bidirectional"))
    )
    (net (code "110") (name "unconnected-(U8-SD2-Pad17)") (class "Default")
      (node (ref "U8") (pin "17") (pinfunction "SD2_17") (pintype "bidirectional"))
    )
    (net (code "111") (name "unconnected-(U8-SD3-Pad18)") (class "Default")
      (node (ref "U8") (pin "18") (pinfunction "SD3_18") (pintype "bidirectional"))
    )
    (net (code "112") (name "unconnected-(U8-SDO-Pad21)") (class "Default")
      (node (ref "U8") (pin "21") (pinfunction "SDO_21") (pintype "bidirectional"))
    )
    (net (code "113") (name "unconnected-(U8-SENSOR_VN-Pad5)") (class "Default")
      (node (ref "U8") (pin "5") (pinfunction "SENSOR_VN_5") (pintype "input"))
    )
    (net (code "114") (name "unconnected-(U8-SENSOR_VP-Pad4)") (class "Default")
      (node (ref "U8") (pin "4") (pinfunction "SENSOR_VP_4") (pintype "input"))
    )
  )
)
